# spdif_xml.net
KiCad netlist of a schematic drawn in EAGLE
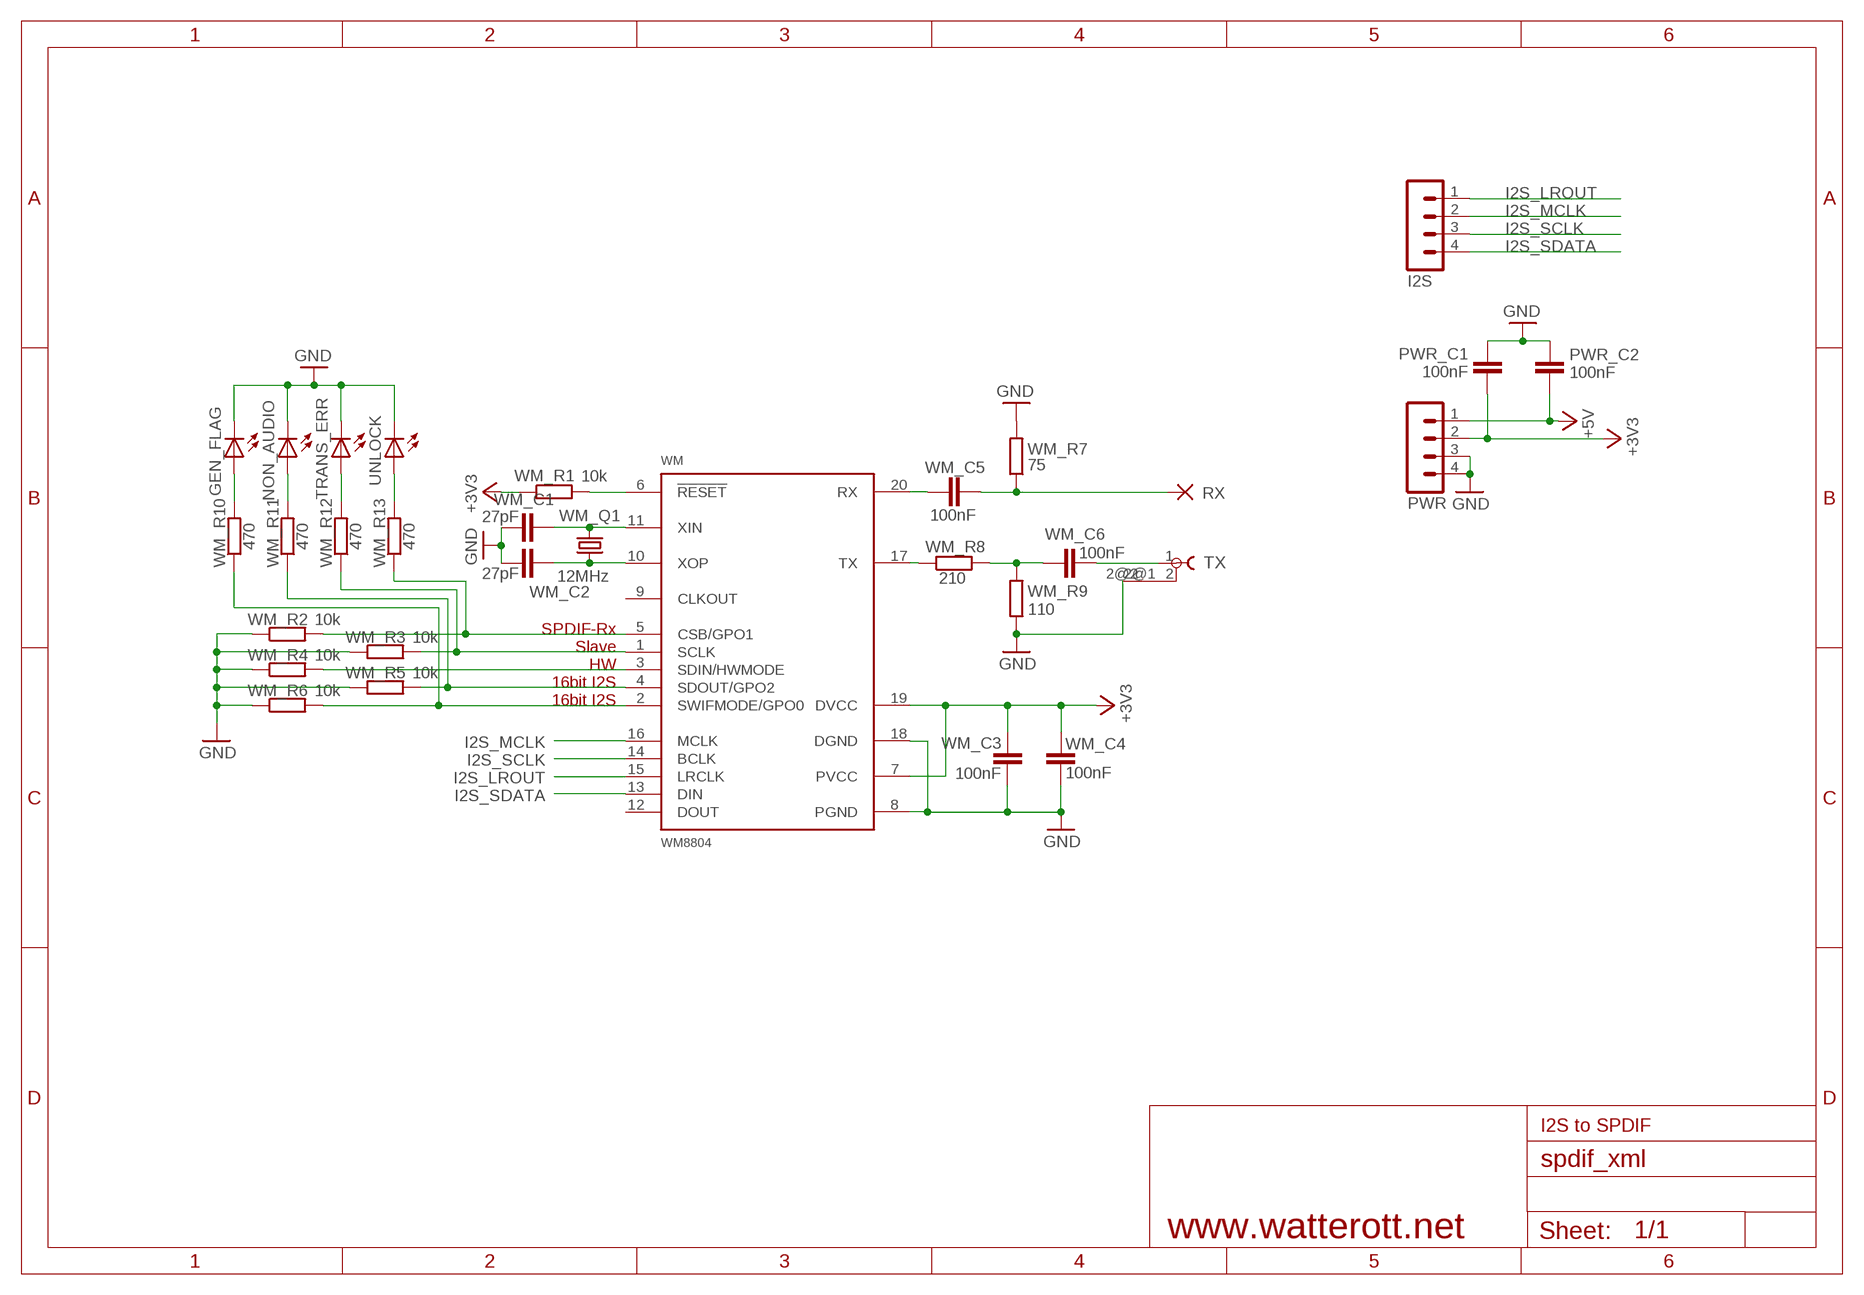
[diagram p0: schematic, sheet 1]

(export (version "E")
  (design (tool "Eeschema 10.0.6"))
  (components
    (comp (ref "GEN_FLAG")
      (value "LEDCHIPLED_0805")
      (footprint "eagle-import:CHIPLED_0805")
      (libsource (lib "eagle-import") (part "LEDCHIPLED_0805"))
    )
    (comp (ref "I2S")
      (value "MA04-1")
      (footprint "eagle-import:MA04-1")
      (libsource (lib "eagle-import") (part "MA04-1"))
    )
    (comp (ref "NON_AUDIO")
      (value "LEDCHIPLED_0805")
      (footprint "eagle-import:CHIPLED_0805")
      (libsource (lib "eagle-import") (part "LEDCHIPLED_0805"))
    )
    (comp (ref "PWR")
      (value "MA04-1")
      (footprint "eagle-import:MA04-1")
      (libsource (lib "eagle-import") (part "MA04-1"))
    )
    (comp (ref "PWR_C1")
      (value "100nF")
      (footprint "eagle-import:C0603")
      (libsource (lib "eagle-import") (part "C-EUC0603"))
    )
    (comp (ref "PWR_C2")
      (value "100nF")
      (footprint "eagle-import:C0603")
      (libsource (lib "eagle-import") (part "C-EUC0603"))
    )
    (comp (ref "RX")
      (value "WIREPAD1,6/0,8")
      (footprint "eagle-import:1,6_0,8")
      (libsource (lib "eagle-import") (part "WIREPAD1,6/0,8"))
    )
    (comp (ref "TRANS_ERR")
      (value "LEDCHIPLED_0805")
      (footprint "eagle-import:CHIPLED_0805")
      (libsource (lib "eagle-import") (part "LEDCHIPLED_0805"))
    )
    (comp (ref "TX")
      (value "TOBU3")
      (footprint "eagle-import:TOBU3")
      (libsource (lib "eagle-import") (part "TOBU3"))
    )
    (comp (ref "UNLOCK")
      (value "LEDCHIPLED_0805")
      (footprint "eagle-import:CHIPLED_0805")
      (libsource (lib "eagle-import") (part "LEDCHIPLED_0805"))
    )
    (comp (ref "WM")
      (value "WM8804")
      (footprint "eagle-import:TSSOP20")
      (libsource (lib "eagle-import") (part "WM8804"))
    )
    (comp (ref "WM_C1")
      (value "27pF")
      (footprint "eagle-import:C0603")
      (libsource (lib "eagle-import") (part "C-EUC0603"))
    )
    (comp (ref "WM_C2")
      (value "27pF")
      (footprint "eagle-import:C0603")
      (libsource (lib "eagle-import") (part "C-EUC0603"))
    )
    (comp (ref "WM_C3")
      (value "100nF")
      (footprint "eagle-import:C0603")
      (libsource (lib "eagle-import") (part "C-EUC0603"))
    )
    (comp (ref "WM_C4")
      (value "100nF")
      (footprint "eagle-import:C0603")
      (libsource (lib "eagle-import") (part "C-EUC0603"))
    )
    (comp (ref "WM_C5")
      (value "100nF")
      (footprint "eagle-import:C0603")
      (libsource (lib "eagle-import") (part "C-EUC0603"))
    )
    (comp (ref "WM_C6")
      (value "100nF")
      (footprint "eagle-import:C0603")
      (libsource (lib "eagle-import") (part "C-EUC0603"))
    )
    (comp (ref "WM_Q1")
      (value "12MHz")
      (footprint "eagle-import:HC49UP")
      (libsource (lib "eagle-import") (part "HC49UP"))
    )
    (comp (ref "WM_R1")
      (value "10k")
      (footprint "eagle-import:R0603")
      (libsource (lib "eagle-import") (part "R-EU_R0603"))
    )
    (comp (ref "WM_R2")
      (value "10k")
      (footprint "eagle-import:R0603")
      (libsource (lib "eagle-import") (part "R-EU_R0603"))
    )
    (comp (ref "WM_R3")
      (value "10k")
      (footprint "eagle-import:R0603")
      (libsource (lib "eagle-import") (part "R-EU_R0603"))
    )
    (comp (ref "WM_R4")
      (value "10k")
      (footprint "eagle-import:R0603")
      (libsource (lib "eagle-import") (part "R-EU_R0603"))
    )
    (comp (ref "WM_R5")
      (value "10k")
      (footprint "eagle-import:R0603")
      (libsource (lib "eagle-import") (part "R-EU_R0603"))
    )
    (comp (ref "WM_R6")
      (value "10k")
      (footprint "eagle-import:R0603")
      (libsource (lib "eagle-import") (part "R-EU_R0603"))
    )
    (comp (ref "WM_R7")
      (value "75")
      (footprint "eagle-import:R0603")
      (libsource (lib "eagle-import") (part "R-EU_R0603"))
    )
    (comp (ref "WM_R8")
      (value "210")
      (footprint "eagle-import:R0603")
      (libsource (lib "eagle-import") (part "R-EU_R0603"))
    )
    (comp (ref "WM_R9")
      (value "110")
      (footprint "eagle-import:R0603")
      (libsource (lib "eagle-import") (part "R-EU_R0603"))
    )
    (comp (ref "WM_R10")
      (value "470")
      (footprint "eagle-import:R0603")
      (libsource (lib "eagle-import") (part "R-EU_R0603"))
    )
    (comp (ref "WM_R11")
      (value "470")
      (footprint "eagle-import:R0603")
      (libsource (lib "eagle-import") (part "R-EU_R0603"))
    )
    (comp (ref "WM_R12")
      (value "470")
      (footprint "eagle-import:R0603")
      (libsource (lib "eagle-import") (part "R-EU_R0603"))
    )
    (comp (ref "WM_R13")
      (value "470")
      (footprint "eagle-import:R0603")
      (libsource (lib "eagle-import") (part "R-EU_R0603"))
    )
  )
  (nets
    (net (code "1") (name "+3V3") (class "Default")
      (node (ref "PWR") (pin "2") (pinfunction "2_2") (pintype "passive"))
      (node (ref "PWR_C1") (pin "2") (pinfunction "2_2") (pintype "passive"))
      (node (ref "WM") (pin "19") (pinfunction "DVCC_19") (pintype "power_in"))
      (node (ref "WM") (pin "7") (pinfunction "PVCC_7") (pintype "power_in"))
      (node (ref "WM_C3") (pin "1") (pinfunction "1_1") (pintype "passive"))
      (node (ref "WM_C4") (pin "1") (pinfunction "1_1") (pintype "passive"))
      (node (ref "WM_R1") (pin "1") (pinfunction "1_1") (pintype "passive"))
    )
    (net (code "2") (name "+5V") (class "Default")
      (node (ref "PWR") (pin "1") (pinfunction "1_1") (pintype "passive"))
      (node (ref "PWR_C2") (pin "2") (pinfunction "2_2") (pintype "passive"))
    )
    (net (code "3") (name "/I2S_LROUT") (class "Default")
      (node (ref "I2S") (pin "1") (pinfunction "1_1") (pintype "passive"))
      (node (ref "WM") (pin "15") (pinfunction "LRCLK_15") (pintype "bidirectional"))
    )
    (net (code "4") (name "/I2S_MCLK") (class "Default")
      (node (ref "I2S") (pin "2") (pinfunction "2_2") (pintype "passive"))
      (node (ref "WM") (pin "16") (pinfunction "MCLK_16") (pintype "bidirectional"))
    )
    (net (code "5") (name "/I2S_SCLK") (class "Default")
      (node (ref "I2S") (pin "3") (pinfunction "3_3") (pintype "passive"))
      (node (ref "WM") (pin "14") (pinfunction "BCLK_14") (pintype "bidirectional"))
    )
    (net (code "6") (name "/I2S_SDATA") (class "Default")
      (node (ref "I2S") (pin "4") (pinfunction "4_4") (pintype "passive"))
      (node (ref "WM") (pin "13") (pinfunction "DIN_13") (pintype "input"))
    )
    (net (code "7") (name "GND") (class "Default")
      (node (ref "GEN_FLAG") (pin "C") (pinfunction "C_C") (pintype "passive"))
      (node (ref "NON_AUDIO") (pin "C") (pinfunction "C_C") (pintype "passive"))
      (node (ref "PWR") (pin "3") (pinfunction "3_3") (pintype "passive"))
      (node (ref "PWR") (pin "4") (pinfunction "4_4") (pintype "passive"))
      (node (ref "PWR_C1") (pin "1") (pinfunction "1_1") (pintype "passive"))
      (node (ref "PWR_C2") (pin "1") (pinfunction "1_1") (pintype "passive"))
      (node (ref "TRANS_ERR") (pin "C") (pinfunction "C_C") (pintype "passive"))
      (node (ref "TX") (pin "2@2") (pinfunction "4_2@2") (pintype "passive"))
      (node (ref "UNLOCK") (pin "C") (pinfunction "C_C") (pintype "passive"))
      (node (ref "WM") (pin "18") (pinfunction "DGND_18") (pintype "power_in"))
      (node (ref "WM") (pin "8") (pinfunction "PGND_8") (pintype "power_in"))
      (node (ref "WM_C1") (pin "2") (pinfunction "2_2") (pintype "passive"))
      (node (ref "WM_C2") (pin "2") (pinfunction "2_2") (pintype "passive"))
      (node (ref "WM_C3") (pin "2") (pinfunction "2_2") (pintype "passive"))
      (node (ref "WM_C4") (pin "2") (pinfunction "2_2") (pintype "passive"))
      (node (ref "WM_R2") (pin "1") (pinfunction "1_1") (pintype "passive"))
      (node (ref "WM_R3") (pin "1") (pinfunction "1_1") (pintype "passive"))
      (node (ref "WM_R4") (pin "1") (pinfunction "1_1") (pintype "passive"))
      (node (ref "WM_R5") (pin "1") (pinfunction "1_1") (pintype "passive"))
      (node (ref "WM_R6") (pin "1") (pinfunction "1_1") (pintype "passive"))
      (node (ref "WM_R7") (pin "2") (pinfunction "2_2") (pintype "passive"))
      (node (ref "WM_R9") (pin "1") (pinfunction "1_1") (pintype "passive"))
    )
    (net (code "8") (name "Net-(GEN_FLAG-PadA)") (class "Default")
      (node (ref "GEN_FLAG") (pin "A") (pinfunction "A_A") (pintype "passive"))
      (node (ref "WM_R10") (pin "2") (pinfunction "2_2") (pintype "passive"))
    )
    (net (code "9") (name "Net-(NON_AUDIO-PadA)") (class "Default")
      (node (ref "NON_AUDIO") (pin "A") (pinfunction "A_A") (pintype "passive"))
      (node (ref "WM_R11") (pin "2") (pinfunction "2_2") (pintype "passive"))
    )
    (net (code "10") (name "Net-(RX-P)") (class "Default")
      (node (ref "RX") (pin "1") (pinfunction "P_1") (pintype "passive"))
      (node (ref "WM_C5") (pin "1") (pinfunction "1_1") (pintype "passive"))
      (node (ref "WM_R7") (pin "1") (pinfunction "1_1") (pintype "passive"))
    )
    (net (code "11") (name "Net-(TRANS_ERR-PadA)") (class "Default")
      (node (ref "TRANS_ERR") (pin "A") (pinfunction "A_A") (pintype "passive"))
      (node (ref "WM_R12") (pin "2") (pinfunction "2_2") (pintype "passive"))
    )
    (net (code "12") (name "Net-(TX-Pad1)") (class "Default")
      (node (ref "TX") (pin "1") (pinfunction "1_1") (pintype "passive"))
      (node (ref "WM_C6") (pin "1") (pinfunction "1_1") (pintype "passive"))
    )
    (net (code "13") (name "Net-(UNLOCK-PadA)") (class "Default")
      (node (ref "UNLOCK") (pin "A") (pinfunction "A_A") (pintype "passive"))
      (node (ref "WM_R13") (pin "2") (pinfunction "2_2") (pintype "passive"))
    )
    (net (code "14") (name "Net-(WM-CSB{slash}GPO1)") (class "Default")
      (node (ref "WM") (pin "5") (pinfunction "CSB/GPO1_5") (pintype "bidirectional"))
      (node (ref "WM_R13") (pin "1") (pinfunction "1_1") (pintype "passive"))
      (node (ref "WM_R2") (pin "2") (pinfunction "2_2") (pintype "passive"))
    )
    (net (code "15") (name "Net-(WM-RX)") (class "Default")
      (node (ref "WM") (pin "20") (pinfunction "RX_20") (pintype "input"))
      (node (ref "WM_C5") (pin "2") (pinfunction "2_2") (pintype "passive"))
    )
    (net (code "16") (name "Net-(WM-SCLK)") (class "Default")
      (node (ref "WM") (pin "1") (pinfunction "SCLK_1") (pintype "bidirectional"))
      (node (ref "WM_R12") (pin "1") (pinfunction "1_1") (pintype "passive"))
      (node (ref "WM_R3") (pin "2") (pinfunction "2_2") (pintype "passive"))
    )
    (net (code "17") (name "Net-(WM-SDIN{slash}HWMODE)") (class "Default")
      (node (ref "WM") (pin "3") (pinfunction "SDIN/HWMODE_3") (pintype "bidirectional"))
      (node (ref "WM_R4") (pin "2") (pinfunction "2_2") (pintype "passive"))
    )
    (net (code "18") (name "Net-(WM-SDOUT{slash}GPO2)") (class "Default")
      (node (ref "WM") (pin "4") (pinfunction "SDOUT/GPO2_4") (pintype "bidirectional"))
      (node (ref "WM_R11") (pin "1") (pinfunction "1_1") (pintype "passive"))
      (node (ref "WM_R5") (pin "2") (pinfunction "2_2") (pintype "passive"))
    )
    (net (code "19") (name "Net-(WM-SWIFMODE{slash}GPO0)") (class "Default")
      (node (ref "WM") (pin "2") (pinfunction "SWIFMODE/GPO0_2") (pintype "bidirectional"))
      (node (ref "WM_R10") (pin "1") (pinfunction "1_1") (pintype "passive"))
      (node (ref "WM_R6") (pin "2") (pinfunction "2_2") (pintype "passive"))
    )
    (net (code "20") (name "Net-(WM-TX)") (class "Default")
      (node (ref "WM") (pin "17") (pinfunction "TX_17") (pintype "output"))
      (node (ref "WM_R8") (pin "1") (pinfunction "1_1") (pintype "passive"))
    )
    (net (code "21") (name "Net-(WM-XIN)") (class "Default")
      (node (ref "WM") (pin "11") (pinfunction "XIN_11") (pintype "bidirectional"))
      (node (ref "WM_C1") (pin "1") (pinfunction "1_1") (pintype "passive"))
      (node (ref "WM_Q1") (pin "2") (pinfunction "2_2") (pintype "passive"))
    )
    (net (code "22") (name "Net-(WM-XOP)") (class "Default")
      (node (ref "WM") (pin "10") (pinfunction "XOP_10") (pintype "output"))
      (node (ref "WM_C2") (pin "1") (pinfunction "1_1") (pintype "passive"))
      (node (ref "WM_Q1") (pin "1") (pinfunction "1_1") (pintype "passive"))
    )
    (net (code "23") (name "Net-(WM-~{RESET})") (class "Default")
      (node (ref "WM") (pin "6") (pinfunction "~{RESET}_6") (pintype "input"))
      (node (ref "WM_R1") (pin "2") (pinfunction "2_2") (pintype "passive"))
    )
    (net (code "24") (name "Net-(WM_C6-Pad2)") (class "Default")
      (node (ref "WM_C6") (pin "2") (pinfunction "2_2") (pintype "passive"))
      (node (ref "WM_R8") (pin "2") (pinfunction "2_2") (pintype "passive"))
      (node (ref "WM_R9") (pin "2") (pinfunction "2_2") (pintype "passive"))
    )
    (net (code "25") (name "unconnected-(TX-3-Pad2@1)") (class "Default")
      (node (ref "TX") (pin "2@1") (pinfunction "3_2@1") (pintype "passive"))
    )
    (net (code "26") (name "unconnected-(TX-Pad2)") (class "Default")
      (node (ref "TX") (pin "2") (pinfunction "2_2") (pintype "passive"))
    )
    (net (code "27") (name "unconnected-(WM-CLKOUT-Pad9)") (class "Default")
      (node (ref "WM") (pin "9") (pinfunction "CLKOUT_9") (pintype "output"))
    )
    (net (code "28") (name "unconnected-(WM-DOUT-Pad12)") (class "Default")
      (node (ref "WM") (pin "12") (pinfunction "DOUT_12") (pintype "output"))
    )
  )
)
